# MOSFET_IF.net
KiCad netlist of a schematic drawn in EAGLE
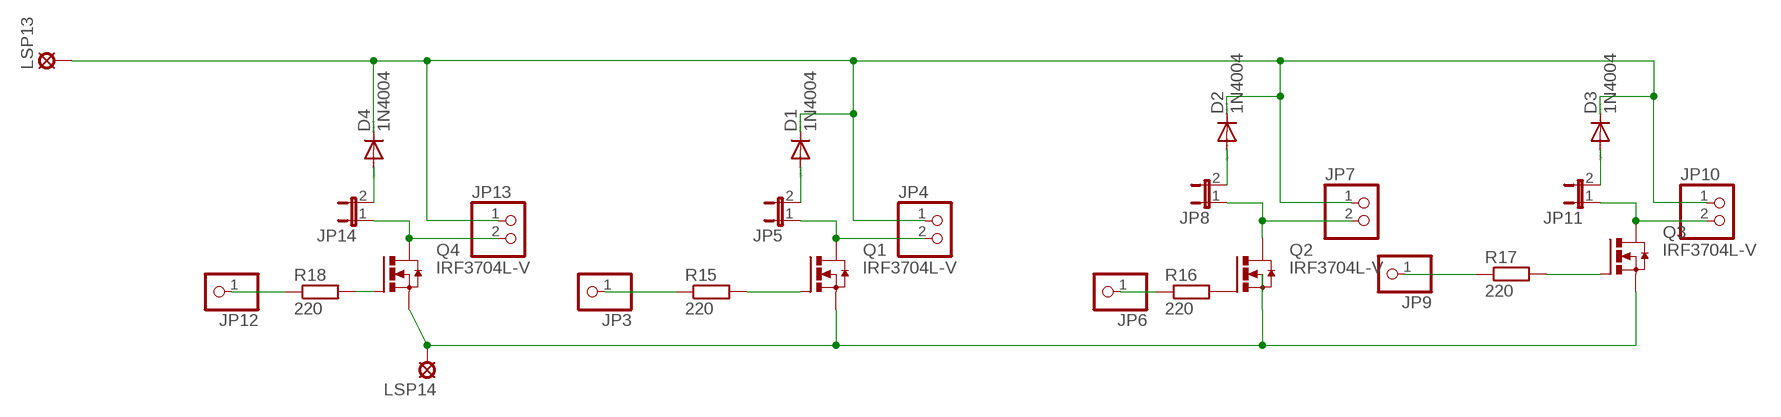
[diagram p0: schematic, sheet 1]

(export (version "E")
  (design (tool "Eeschema 10.0.6"))
  (components
    (comp (ref "D1")
      (value "1N4004")
      (footprint "eagle-import:DO41-10")
      (libsource (lib "eagle-import") (part "1N4004"))
    )
    (comp (ref "D2")
      (value "1N4004")
      (footprint "eagle-import:DO41-10")
      (libsource (lib "eagle-import") (part "1N4004"))
    )
    (comp (ref "D3")
      (value "1N4004")
      (footprint "eagle-import:DO41-10")
      (libsource (lib "eagle-import") (part "1N4004"))
    )
    (comp (ref "D4")
      (value "1N4004")
      (footprint "eagle-import:DO41-10")
      (libsource (lib "eagle-import") (part "1N4004"))
    )
    (comp (ref "JP3")
      (value "PINHD-1X1")
      (footprint "eagle-import:1X01")
      (libsource (lib "eagle-import") (part "PINHD-1X1"))
    )
    (comp (ref "JP4")
      (value "PINHD-1X2")
      (footprint "eagle-import:1X02")
      (libsource (lib "eagle-import") (part "PINHD-1X2"))
    )
    (comp (ref "JP5")
      (value "JP1E")
      (footprint "eagle-import:JP1")
      (libsource (lib "eagle-import") (part "JP1E"))
    )
    (comp (ref "JP6")
      (value "PINHD-1X1")
      (footprint "eagle-import:1X01")
      (libsource (lib "eagle-import") (part "PINHD-1X1"))
    )
    (comp (ref "JP7")
      (value "PINHD-1X2")
      (footprint "eagle-import:1X02")
      (libsource (lib "eagle-import") (part "PINHD-1X2"))
    )
    (comp (ref "JP8")
      (value "JP1E")
      (footprint "eagle-import:JP1")
      (libsource (lib "eagle-import") (part "JP1E"))
    )
    (comp (ref "JP9")
      (value "PINHD-1X1")
      (footprint "eagle-import:1X01")
      (libsource (lib "eagle-import") (part "PINHD-1X1"))
    )
    (comp (ref "JP10")
      (value "PINHD-1X2")
      (footprint "eagle-import:1X02")
      (libsource (lib "eagle-import") (part "PINHD-1X2"))
    )
    (comp (ref "JP11")
      (value "JP1E")
      (footprint "eagle-import:JP1")
      (libsource (lib "eagle-import") (part "JP1E"))
    )
    (comp (ref "JP12")
      (value "PINHD-1X1")
      (footprint "eagle-import:1X01")
      (libsource (lib "eagle-import") (part "PINHD-1X1"))
    )
    (comp (ref "JP13")
      (value "PINHD-1X2")
      (footprint "eagle-import:1X02")
      (libsource (lib "eagle-import") (part "PINHD-1X2"))
    )
    (comp (ref "JP14")
      (value "JP1E")
      (footprint "eagle-import:JP1")
      (libsource (lib "eagle-import") (part "JP1E"))
    )
    (comp (ref "LSP13")
      (value "LSP10")
      (footprint "eagle-import:LSP10")
      (libsource (lib "eagle-import") (part "LSP10"))
    )
    (comp (ref "LSP14")
      (value "LSP10")
      (footprint "eagle-import:LSP10")
      (libsource (lib "eagle-import") (part "LSP10"))
    )
    (comp (ref "Q1")
      (value "IRF3704L-V")
      (footprint "eagle-import:TO262-V")
      (libsource (lib "eagle-import") (part "IRF3704L-V"))
    )
    (comp (ref "Q2")
      (value "IRF3704L-V")
      (footprint "eagle-import:TO262-V")
      (libsource (lib "eagle-import") (part "IRF3704L-V"))
    )
    (comp (ref "Q3")
      (value "IRF3704L-V")
      (footprint "eagle-import:TO262-V")
      (libsource (lib "eagle-import") (part "IRF3704L-V"))
    )
    (comp (ref "Q4")
      (value "IRF3704L-V")
      (footprint "eagle-import:TO262-V")
      (libsource (lib "eagle-import") (part "IRF3704L-V"))
    )
    (comp (ref "R15")
      (value "220")
      (footprint "eagle-import:0207_10")
      (libsource (lib "eagle-import") (part "R-EU_0207/10"))
    )
    (comp (ref "R16")
      (value "220")
      (footprint "eagle-import:0207_10")
      (libsource (lib "eagle-import") (part "R-EU_0207/10"))
    )
    (comp (ref "R17")
      (value "220")
      (footprint "eagle-import:0207_10")
      (libsource (lib "eagle-import") (part "R-EU_0207/10"))
    )
    (comp (ref "R18")
      (value "220")
      (footprint "eagle-import:0207_10")
      (libsource (lib "eagle-import") (part "R-EU_0207/10"))
    )
  )
  (nets
    (net (code "1") (name "Net-(D1-PadA)") (class "Default")
      (node (ref "D1") (pin "A") (pinfunction "A_A") (pintype "passive"))
      (node (ref "JP5") (pin "2") (pinfunction "2_2") (pintype "passive"))
    )
    (net (code "2") (name "Net-(D1-PadC)") (class "Default")
      (node (ref "D1") (pin "C") (pinfunction "C_C") (pintype "passive"))
      (node (ref "D2") (pin "C") (pinfunction "C_C") (pintype "passive"))
      (node (ref "D3") (pin "C") (pinfunction "C_C") (pintype "passive"))
      (node (ref "D4") (pin "C") (pinfunction "C_C") (pintype "passive"))
      (node (ref "JP10") (pin "1") (pinfunction "1_1") (pintype "passive"))
      (node (ref "JP13") (pin "1") (pinfunction "1_1") (pintype "passive"))
      (node (ref "JP4") (pin "1") (pinfunction "1_1") (pintype "passive"))
      (node (ref "JP7") (pin "1") (pinfunction "1_1") (pintype "passive"))
      (node (ref "LSP13") (pin "MP") (pinfunction "MP_MP") (pintype "passive"))
    )
    (net (code "3") (name "Net-(D2-PadA)") (class "Default")
      (node (ref "D2") (pin "A") (pinfunction "A_A") (pintype "passive"))
      (node (ref "JP8") (pin "2") (pinfunction "2_2") (pintype "passive"))
    )
    (net (code "4") (name "Net-(D3-PadA)") (class "Default")
      (node (ref "D3") (pin "A") (pinfunction "A_A") (pintype "passive"))
      (node (ref "JP11") (pin "2") (pinfunction "2_2") (pintype "passive"))
    )
    (net (code "5") (name "Net-(D4-PadA)") (class "Default")
      (node (ref "D4") (pin "A") (pinfunction "A_A") (pintype "passive"))
      (node (ref "JP14") (pin "2") (pinfunction "2_2") (pintype "passive"))
    )
    (net (code "6") (name "Net-(JP3-Pad1)") (class "Default")
      (node (ref "JP3") (pin "1") (pinfunction "1_1") (pintype "passive"))
      (node (ref "R15") (pin "1") (pinfunction "1_1") (pintype "passive"))
    )
    (net (code "7") (name "Net-(JP6-Pad1)") (class "Default")
      (node (ref "JP6") (pin "1") (pinfunction "1_1") (pintype "passive"))
      (node (ref "R16") (pin "1") (pinfunction "1_1") (pintype "passive"))
    )
    (net (code "8") (name "Net-(JP9-Pad1)") (class "Default")
      (node (ref "JP9") (pin "1") (pinfunction "1_1") (pintype "passive"))
      (node (ref "R17") (pin "1") (pinfunction "1_1") (pintype "passive"))
    )
    (net (code "9") (name "Net-(JP12-Pad1)") (class "Default")
      (node (ref "JP12") (pin "1") (pinfunction "1_1") (pintype "passive"))
      (node (ref "R18") (pin "1") (pinfunction "1_1") (pintype "passive"))
    )
    (net (code "10") (name "Net-(Q1-D)") (class "Default")
      (node (ref "JP4") (pin "2") (pinfunction "2_2") (pintype "passive"))
      (node (ref "JP5") (pin "1") (pinfunction "1_1") (pintype "passive"))
      (node (ref "Q1") (pin "2") (pinfunction "D_2") (pintype "passive"))
    )
    (net (code "11") (name "Net-(Q1-G)") (class "Default")
      (node (ref "Q1") (pin "1") (pinfunction "G_1") (pintype "passive"))
      (node (ref "R15") (pin "2") (pinfunction "2_2") (pintype "passive"))
    )
    (net (code "12") (name "Net-(Q1-S)") (class "Default")
      (node (ref "LSP14") (pin "MP") (pinfunction "MP_MP") (pintype "passive"))
      (node (ref "Q1") (pin "3") (pinfunction "S_3") (pintype "passive"))
      (node (ref "Q2") (pin "3") (pinfunction "S_3") (pintype "passive"))
      (node (ref "Q3") (pin "3") (pinfunction "S_3") (pintype "passive"))
      (node (ref "Q4") (pin "3") (pinfunction "S_3") (pintype "passive"))
    )
    (net (code "13") (name "Net-(Q2-D)") (class "Default")
      (node (ref "JP7") (pin "2") (pinfunction "2_2") (pintype "passive"))
      (node (ref "JP8") (pin "1") (pinfunction "1_1") (pintype "passive"))
      (node (ref "Q2") (pin "2") (pinfunction "D_2") (pintype "passive"))
    )
    (net (code "14") (name "Net-(Q2-G)") (class "Default")
      (node (ref "Q2") (pin "1") (pinfunction "G_1") (pintype "passive"))
      (node (ref "R16") (pin "2") (pinfunction "2_2") (pintype "passive"))
    )
    (net (code "15") (name "Net-(Q3-D)") (class "Default")
      (node (ref "JP10") (pin "2") (pinfunction "2_2") (pintype "passive"))
      (node (ref "JP11") (pin "1") (pinfunction "1_1") (pintype "passive"))
      (node (ref "Q3") (pin "2") (pinfunction "D_2") (pintype "passive"))
    )
    (net (code "16") (name "Net-(Q3-G)") (class "Default")
      (node (ref "Q3") (pin "1") (pinfunction "G_1") (pintype "passive"))
      (node (ref "R17") (pin "2") (pinfunction "2_2") (pintype "passive"))
    )
    (net (code "17") (name "Net-(Q4-D)") (class "Default")
      (node (ref "JP13") (pin "2") (pinfunction "2_2") (pintype "passive"))
      (node (ref "JP14") (pin "1") (pinfunction "1_1") (pintype "passive"))
      (node (ref "Q4") (pin "2") (pinfunction "D_2") (pintype "passive"))
    )
    (net (code "18") (name "Net-(Q4-G)") (class "Default")
      (node (ref "Q4") (pin "1") (pinfunction "G_1") (pintype "passive"))
      (node (ref "R18") (pin "2") (pinfunction "2_2") (pintype "passive"))
    )
  )
)
